# MainBoardR2.net
KiCad netlist of a schematic drawn in EAGLE
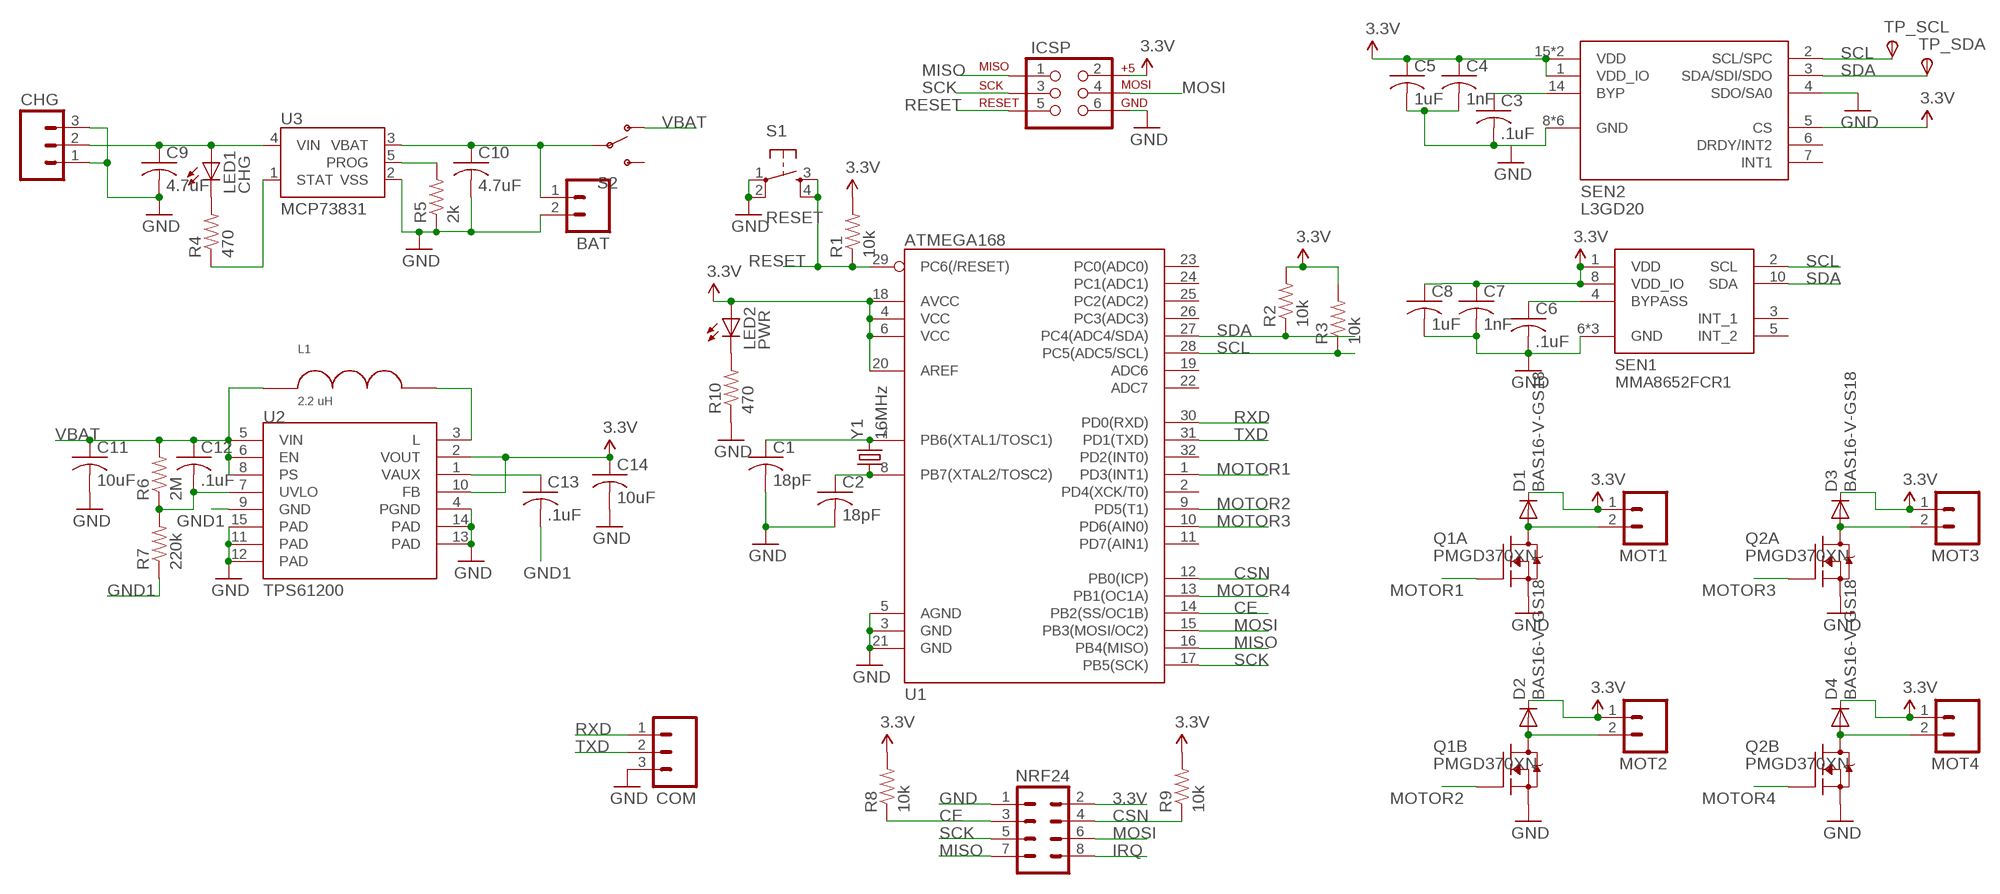
[diagram p0: schematic, sheet 1]

(export (version "E")
  (design (tool "Eeschema 10.0.6"))
  (components
    (comp (ref "BAT")
      (value "M02LOCK_LONGPADS")
      (footprint "eagle-import:1X02_LOCK_LONGPADS")
      (libsource (lib "eagle-import") (part "M02LOCK_LONGPADS"))
    )
    (comp (ref "C1")
      (value "18pF")
      (footprint "eagle-import:C0805")
      (libsource (lib "eagle-import") (part "C-USC0805"))
    )
    (comp (ref "C2")
      (value "18pF")
      (footprint "eagle-import:C0805")
      (libsource (lib "eagle-import") (part "C-USC0805"))
    )
    (comp (ref "C3")
      (value ".1uF")
      (footprint "eagle-import:C0805")
      (libsource (lib "eagle-import") (part "C-USC0805"))
    )
    (comp (ref "C4")
      (value "1nF")
      (footprint "eagle-import:C0805")
      (libsource (lib "eagle-import") (part "C-USC0805"))
    )
    (comp (ref "C5")
      (value "1uF")
      (footprint "eagle-import:C0805")
      (libsource (lib "eagle-import") (part "C-USC0805"))
    )
    (comp (ref "C6")
      (value ".1uF")
      (footprint "eagle-import:C0805")
      (libsource (lib "eagle-import") (part "C-USC0805"))
    )
    (comp (ref "C7")
      (value "1nF")
      (footprint "eagle-import:C0805")
      (libsource (lib "eagle-import") (part "C-USC0805"))
    )
    (comp (ref "C8")
      (value "1uF")
      (footprint "eagle-import:C0805")
      (libsource (lib "eagle-import") (part "C-USC0805"))
    )
    (comp (ref "C9")
      (value "4.7uF")
      (footprint "eagle-import:C0805")
      (libsource (lib "eagle-import") (part "C-USC0805"))
    )
    (comp (ref "C10")
      (value "4.7uF")
      (footprint "eagle-import:C0805")
      (libsource (lib "eagle-import") (part "C-USC0805"))
    )
    (comp (ref "C11")
      (value "10uF")
      (footprint "eagle-import:C0805")
      (libsource (lib "eagle-import") (part "C-USC0805"))
    )
    (comp (ref "C12")
      (value ".1uF")
      (footprint "eagle-import:C0805")
      (libsource (lib "eagle-import") (part "C-USC0805"))
    )
    (comp (ref "C13")
      (value ".1uF")
      (footprint "eagle-import:C0805")
      (libsource (lib "eagle-import") (part "C-USC0805"))
    )
    (comp (ref "C14")
      (value "10uF")
      (footprint "eagle-import:C0805")
      (libsource (lib "eagle-import") (part "C-USC0805"))
    )
    (comp (ref "CHG")
      (value "M03LONGPADS")
      (footprint "eagle-import:1X03_LONGPADS")
      (libsource (lib "eagle-import") (part "M03LONGPADS"))
    )
    (comp (ref "COM")
      (value "M03LONGPADS")
      (footprint "eagle-import:1X03_LONGPADS")
      (libsource (lib "eagle-import") (part "M03LONGPADS"))
    )
    (comp (ref "D1")
      (value "BAS16-V-GS18")
      (footprint "eagle-import:SOT23")
      (libsource (lib "eagle-import") (part "BAS16-V-GS18"))
    )
    (comp (ref "D2")
      (value "BAS16-V-GS18")
      (footprint "eagle-import:SOT23")
      (libsource (lib "eagle-import") (part "BAS16-V-GS18"))
    )
    (comp (ref "D3")
      (value "BAS16-V-GS18")
      (footprint "eagle-import:SOT23")
      (libsource (lib "eagle-import") (part "BAS16-V-GS18"))
    )
    (comp (ref "D4")
      (value "BAS16-V-GS18")
      (footprint "eagle-import:SOT23")
      (libsource (lib "eagle-import") (part "BAS16-V-GS18"))
    )
    (comp (ref "ICSP")
      (value "AVR_SPI_PRG_62X3_LOCK")
      (footprint "eagle-import:2X3_LOCK")
      (libsource (lib "eagle-import") (part "AVR_SPI_PRG_62X3_LOCK"))
    )
    (comp (ref "L1")
      (value "2.2 uH")
      (footprint "eagle-import:2518")
      (libsource (lib "eagle-import") (part "BRHL2518T2R2M"))
    )
    (comp (ref "LED1")
      (value "CHG")
      (footprint "eagle-import:LED-1206")
      (libsource (lib "eagle-import") (part "LED1206"))
    )
    (comp (ref "LED2")
      (value "PWR")
      (footprint "eagle-import:LED-1206")
      (libsource (lib "eagle-import") (part "LED1206"))
    )
    (comp (ref "MOT1")
      (value "M02LOCK_LONGPADS")
      (footprint "eagle-import:1X02_LOCK_LONGPADS")
      (libsource (lib "eagle-import") (part "M02LOCK_LONGPADS"))
    )
    (comp (ref "MOT2")
      (value "M02LOCK_LONGPADS")
      (footprint "eagle-import:1X02_LOCK_LONGPADS")
      (libsource (lib "eagle-import") (part "M02LOCK_LONGPADS"))
    )
    (comp (ref "MOT3")
      (value "M02LOCK_LONGPADS")
      (footprint "eagle-import:1X02_LOCK_LONGPADS")
      (libsource (lib "eagle-import") (part "M02LOCK_LONGPADS"))
    )
    (comp (ref "MOT4")
      (value "M02LOCK_LONGPADS")
      (footprint "eagle-import:1X02_LOCK_LONGPADS")
      (libsource (lib "eagle-import") (part "M02LOCK_LONGPADS"))
    )
    (comp (ref "NRF24")
      (value "M04X2")
      (footprint "eagle-import:2X4")
      (libsource (lib "eagle-import") (part "M04X2"))
    )
    (comp (ref "Q1")
      (value "PMGD370XN")
      (footprint "eagle-import:SOT363_INFINEON")
      (libsource (lib "eagle-import") (part "PMGD370XN"))
    )
    (comp (ref "Q2")
      (value "PMGD370XN")
      (footprint "eagle-import:SOT363_INFINEON")
      (libsource (lib "eagle-import") (part "PMGD370XN"))
    )
    (comp (ref "R1")
      (value "10k")
      (footprint "eagle-import:0805")
      (libsource (lib "eagle-import") (part "RESISTOR0805-RES"))
    )
    (comp (ref "R2")
      (value "10k")
      (footprint "eagle-import:0805")
      (libsource (lib "eagle-import") (part "RESISTOR0805-RES"))
    )
    (comp (ref "R3")
      (value "10k")
      (footprint "eagle-import:0805")
      (libsource (lib "eagle-import") (part "RESISTOR0805-RES"))
    )
    (comp (ref "R4")
      (value "470")
      (footprint "eagle-import:0805")
      (libsource (lib "eagle-import") (part "RESISTOR0805-RES"))
    )
    (comp (ref "R5")
      (value "2k")
      (footprint "eagle-import:0805")
      (libsource (lib "eagle-import") (part "RESISTOR0805-RES"))
    )
    (comp (ref "R6")
      (value "2M")
      (footprint "eagle-import:0805")
      (libsource (lib "eagle-import") (part "RESISTOR0805-RES"))
    )
    (comp (ref "R7")
      (value "220k")
      (footprint "eagle-import:0805")
      (libsource (lib "eagle-import") (part "RESISTOR0805-RES"))
    )
    (comp (ref "R8")
      (value "10k")
      (footprint "eagle-import:0805")
      (libsource (lib "eagle-import") (part "RESISTOR0805-RES"))
    )
    (comp (ref "R9")
      (value "10k")
      (footprint "eagle-import:0805")
      (libsource (lib "eagle-import") (part "RESISTOR0805-RES"))
    )
    (comp (ref "R10")
      (value "470")
      (footprint "eagle-import:0805")
      (libsource (lib "eagle-import") (part "RESISTOR0805-RES"))
    )
    (comp (ref "S1")
      (value "RESET")
      (footprint "eagle-import:TACTILE_SWITCH_SMD")
      (libsource (lib "eagle-import") (part "TAC_SWITCHSMD"))
    )
    (comp (ref "S2")
      (value "SWITCH-SPST-SMD-A")
      (footprint "eagle-import:SWITCH-SPST-SMD-A")
      (libsource (lib "eagle-import") (part "SWITCH-SPST-SMD-A"))
    )
    (comp (ref "SEN1")
      (value "MMA8652FCR1")
      (footprint "eagle-import:10_PIN_DFN")
      (libsource (lib "eagle-import") (part "MMA8652FCR1"))
    )
    (comp (ref "SEN2")
      (value "L3GD20")
      (footprint "eagle-import:LGA-16")
      (libsource (lib "eagle-import") (part "L3GD20"))
    )
    (comp (ref "TP_SCL")
      (value "TPSTP14SQ")
      (footprint "eagle-import:TP14SQ")
      (libsource (lib "eagle-import") (part "TPSTP14SQ"))
    )
    (comp (ref "TP_SDA")
      (value "TPSTP14SQ")
      (footprint "eagle-import:TP14SQ")
      (libsource (lib "eagle-import") (part "TPSTP14SQ"))
    )
    (comp (ref "U1")
      (value "ATMEGA168")
      (footprint "eagle-import:TQFP32-08")
      (libsource (lib "eagle-import") (part "ATMEGA168"))
    )
    (comp (ref "U2")
      (value "TPS61200")
      (footprint "eagle-import:QFN-10_PAD")
      (libsource (lib "eagle-import") (part "TPS61200"))
    )
    (comp (ref "U3")
      (value "MCP73831")
      (footprint "eagle-import:SOT23-5")
      (libsource (lib "eagle-import") (part "MCP73831"))
    )
    (comp (ref "Y1")
      (value "16MHz")
      (footprint "eagle-import:CRYSTAL-SMD-10.5X4.8-2PIN")
      (libsource (lib "eagle-import") (part "CRYSTAL10.5X4.8"))
    )
  )
  (nets
    (net (code "1") (name "/CE") (class "Default")
      (node (ref "NRF24") (pin "3") (pinfunction "3_3") (pintype "passive"))
      (node (ref "R8") (pin "1") (pinfunction "1_1") (pintype "passive"))
      (node (ref "U1") (pin "14") (pinfunction "PB2(SS/OC1B)_14") (pintype "bidirectional"))
    )
    (net (code "2") (name "/CSN") (class "Default")
      (node (ref "NRF24") (pin "4") (pinfunction "4_4") (pintype "passive"))
      (node (ref "R9") (pin "1") (pinfunction "1_1") (pintype "passive"))
      (node (ref "U1") (pin "12") (pinfunction "PB0(ICP)_12") (pintype "bidirectional"))
    )
    (net (code "3") (name "/GND1") (class "Default")
      (node (ref "C13") (pin "2") (pinfunction "2_2") (pintype "passive"))
      (node (ref "R7") (pin "1") (pinfunction "1_1") (pintype "passive"))
      (node (ref "U2") (pin "9") (pinfunction "GND_9") (pintype "power_in"))
    )
    (net (code "4") (name "/IRQ") (class "Default")
      (node (ref "NRF24") (pin "8") (pinfunction "8_8") (pintype "passive"))
    )
    (net (code "5") (name "/MISO") (class "Default")
      (node (ref "ICSP") (pin "1") (pinfunction "1_1") (pintype "passive"))
      (node (ref "NRF24") (pin "7") (pinfunction "7_7") (pintype "passive"))
      (node (ref "U1") (pin "16") (pinfunction "PB4(MISO)_16") (pintype "bidirectional"))
    )
    (net (code "6") (name "/MOSI") (class "Default")
      (node (ref "ICSP") (pin "4") (pinfunction "4_4") (pintype "passive"))
      (node (ref "NRF24") (pin "6") (pinfunction "6_6") (pintype "passive"))
      (node (ref "U1") (pin "15") (pinfunction "PB3(MOSI/OC2)_15") (pintype "bidirectional"))
    )
    (net (code "7") (name "/MOTOR1") (class "Default")
      (node (ref "Q1") (pin "2") (pinfunction "G_2") (pintype "passive"))
      (node (ref "U1") (pin "1") (pinfunction "PD3(INT1)_1") (pintype "bidirectional"))
    )
    (net (code "8") (name "/MOTOR2") (class "Default")
      (node (ref "Q1") (pin "5") (pinfunction "G_5") (pintype "passive"))
      (node (ref "U1") (pin "9") (pinfunction "PD5(T1)_9") (pintype "bidirectional"))
    )
    (net (code "9") (name "/MOTOR3") (class "Default")
      (node (ref "Q2") (pin "2") (pinfunction "G_2") (pintype "passive"))
      (node (ref "U1") (pin "10") (pinfunction "PD6(AIN0)_10") (pintype "bidirectional"))
    )
    (net (code "10") (name "/MOTOR4") (class "Default")
      (node (ref "Q2") (pin "5") (pinfunction "G_5") (pintype "passive"))
      (node (ref "U1") (pin "13") (pinfunction "PB1(OC1A)_13") (pintype "bidirectional"))
    )
    (net (code "11") (name "/RESET") (class "Default")
      (node (ref "ICSP") (pin "5") (pinfunction "5_5") (pintype "passive"))
      (node (ref "R1") (pin "1") (pinfunction "1_1") (pintype "passive"))
      (node (ref "S1") (pin "3") (pinfunction "3_3") (pintype "passive"))
      (node (ref "S1") (pin "4") (pinfunction "4_4") (pintype "passive"))
      (node (ref "U1") (pin "29") (pinfunction "PC6(/RESET)_29") (pintype "bidirectional"))
    )
    (net (code "12") (name "/RXD") (class "Default")
      (node (ref "COM") (pin "1") (pinfunction "1_1") (pintype "passive"))
      (node (ref "U1") (pin "30") (pinfunction "PD0(RXD)_30") (pintype "bidirectional"))
    )
    (net (code "13") (name "/SCK") (class "Default")
      (node (ref "ICSP") (pin "3") (pinfunction "3_3") (pintype "passive"))
      (node (ref "NRF24") (pin "5") (pinfunction "5_5") (pintype "passive"))
      (node (ref "U1") (pin "17") (pinfunction "PB5(SCK)_17") (pintype "bidirectional"))
    )
    (net (code "14") (name "/SCL") (class "Default")
      (node (ref "R3") (pin "1") (pinfunction "1_1") (pintype "passive"))
      (node (ref "SEN1") (pin "2") (pinfunction "SCL_2") (pintype "bidirectional"))
      (node (ref "SEN2") (pin "2") (pinfunction "SCL/SPC_2") (pintype "bidirectional"))
      (node (ref "TP_SCL") (pin "TP") (pinfunction "PP_TP") (pintype "input"))
      (node (ref "U1") (pin "28") (pinfunction "PC5(ADC5/SCL)_28") (pintype "bidirectional"))
    )
    (net (code "15") (name "/SDA") (class "Default")
      (node (ref "R2") (pin "1") (pinfunction "1_1") (pintype "passive"))
      (node (ref "SEN1") (pin "10") (pinfunction "SDA_10") (pintype "bidirectional"))
      (node (ref "SEN2") (pin "3") (pinfunction "SDA/SDI/SDO_3") (pintype "bidirectional"))
      (node (ref "TP_SDA") (pin "TP") (pinfunction "PP_TP") (pintype "input"))
      (node (ref "U1") (pin "27") (pinfunction "PC4(ADC4/SDA)_27") (pintype "bidirectional"))
    )
    (net (code "16") (name "/TXD") (class "Default")
      (node (ref "COM") (pin "2") (pinfunction "2_2") (pintype "passive"))
      (node (ref "U1") (pin "31") (pinfunction "PD1(TXD)_31") (pintype "bidirectional"))
    )
    (net (code "17") (name "/VBAT") (class "Default")
      (node (ref "C11") (pin "1") (pinfunction "1_1") (pintype "passive"))
      (node (ref "C12") (pin "1") (pinfunction "1_1") (pintype "passive"))
      (node (ref "L1") (pin "P$1") (pinfunction "1_P$1") (pintype "bidirectional"))
      (node (ref "R6") (pin "2") (pinfunction "2_2") (pintype "passive"))
      (node (ref "S2") (pin "1") (pinfunction "O_1") (pintype "passive"))
      (node (ref "U2") (pin "5") (pinfunction "VIN_5") (pintype "power_in"))
      (node (ref "U2") (pin "6") (pinfunction "EN_6") (pintype "input"))
      (node (ref "U2") (pin "8") (pinfunction "PS_8") (pintype "input"))
    )
    (net (code "18") (name "3.3V") (class "Default")
      (node (ref "C14") (pin "1") (pinfunction "1_1") (pintype "passive"))
      (node (ref "C4") (pin "1") (pinfunction "1_1") (pintype "passive"))
      (node (ref "C5") (pin "1") (pinfunction "1_1") (pintype "passive"))
      (node (ref "C7") (pin "1") (pinfunction "1_1") (pintype "passive"))
      (node (ref "C8") (pin "1") (pinfunction "1_1") (pintype "passive"))
      (node (ref "D1") (pin "3") (pinfunction "C_3") (pintype "passive"))
      (node (ref "D2") (pin "3") (pinfunction "C_3") (pintype "passive"))
      (node (ref "D3") (pin "3") (pinfunction "C_3") (pintype "passive"))
      (node (ref "D4") (pin "3") (pinfunction "C_3") (pintype "passive"))
      (node (ref "ICSP") (pin "2") (pinfunction "2_2") (pintype "passive"))
      (node (ref "LED2") (pin "A") (pinfunction "A_A") (pintype "passive"))
      (node (ref "MOT1") (pin "1") (pinfunction "1_1") (pintype "passive"))
      (node (ref "MOT2") (pin "1") (pinfunction "1_1") (pintype "passive"))
      (node (ref "MOT3") (pin "1") (pinfunction "1_1") (pintype "passive"))
      (node (ref "MOT4") (pin "1") (pinfunction "1_1") (pintype "passive"))
      (node (ref "NRF24") (pin "2") (pinfunction "2_2") (pintype "passive"))
      (node (ref "R1") (pin "2") (pinfunction "2_2") (pintype "passive"))
      (node (ref "R2") (pin "2") (pinfunction "2_2") (pintype "passive"))
      (node (ref "R3") (pin "2") (pinfunction "2_2") (pintype "passive"))
      (node (ref "R8") (pin "2") (pinfunction "2_2") (pintype "passive"))
      (node (ref "R9") (pin "2") (pinfunction "2_2") (pintype "passive"))
      (node (ref "SEN1") (pin "1") (pinfunction "VDD_1") (pintype "bidirectional"))
      (node (ref "SEN1") (pin "8") (pinfunction "VDD_IO_8") (pintype "bidirectional"))
      (node (ref "SEN2") (pin "1") (pinfunction "VDD_IO_1") (pintype "bidirectional"))
      (node (ref "SEN2") (pin "15") (pinfunction "VDD_15") (pintype "bidirectional"))
      (node (ref "SEN2") (pin "16") (pinfunction "VDD_16") (pintype "bidirectional"))
      (node (ref "SEN2") (pin "5") (pinfunction "CS_5") (pintype "bidirectional"))
      (node (ref "U1") (pin "18") (pinfunction "AVCC_18") (pintype "bidirectional"))
      (node (ref "U1") (pin "20") (pinfunction "AREF_20") (pintype "bidirectional"))
      (node (ref "U1") (pin "4") (pinfunction "VCC_4") (pintype "bidirectional"))
      (node (ref "U1") (pin "6") (pinfunction "VCC_6") (pintype "bidirectional"))
      (node (ref "U2") (pin "10") (pinfunction "FB_10") (pintype "passive"))
      (node (ref "U2") (pin "2") (pinfunction "VOUT_2") (pintype "passive"))
    )
    (net (code "19") (name "GND") (class "Default")
      (node (ref "BAT") (pin "2") (pinfunction "2_2") (pintype "passive"))
      (node (ref "C1") (pin "2") (pinfunction "2_2") (pintype "passive"))
      (node (ref "C10") (pin "2") (pinfunction "2_2") (pintype "passive"))
      (node (ref "C11") (pin "2") (pinfunction "2_2") (pintype "passive"))
      (node (ref "C14") (pin "2") (pinfunction "2_2") (pintype "passive"))
      (node (ref "C2") (pin "2") (pinfunction "2_2") (pintype "passive"))
      (node (ref "C3") (pin "2") (pinfunction "2_2") (pintype "passive"))
      (node (ref "C4") (pin "2") (pinfunction "2_2") (pintype "passive"))
      (node (ref "C5") (pin "2") (pinfunction "2_2") (pintype "passive"))
      (node (ref "C6") (pin "2") (pinfunction "2_2") (pintype "passive"))
      (node (ref "C7") (pin "2") (pinfunction "2_2") (pintype "passive"))
      (node (ref "C8") (pin "2") (pinfunction "2_2") (pintype "passive"))
      (node (ref "C9") (pin "2") (pinfunction "2_2") (pintype "passive"))
      (node (ref "CHG") (pin "1") (pinfunction "1_1") (pintype "passive"))
      (node (ref "CHG") (pin "3") (pinfunction "3_3") (pintype "passive"))
      (node (ref "COM") (pin "3") (pinfunction "3_3") (pintype "passive"))
      (node (ref "ICSP") (pin "6") (pinfunction "6_6") (pintype "passive"))
      (node (ref "NRF24") (pin "1") (pinfunction "1_1") (pintype "passive"))
      (node (ref "Q1") (pin "1") (pinfunction "S_1") (pintype "passive"))
      (node (ref "Q1") (pin "4") (pinfunction "S_4") (pintype "passive"))
      (node (ref "Q2") (pin "1") (pinfunction "S_1") (pintype "passive"))
      (node (ref "Q2") (pin "4") (pinfunction "S_4") (pintype "passive"))
      (node (ref "R10") (pin "1") (pinfunction "1_1") (pintype "passive"))
      (node (ref "R5") (pin "1") (pinfunction "1_1") (pintype "passive"))
      (node (ref "S1") (pin "1") (pinfunction "1_1") (pintype "passive"))
      (node (ref "S1") (pin "2") (pinfunction "2_2") (pintype "passive"))
      (node (ref "SEN1") (pin "6") (pinfunction "GND_6") (pintype "bidirectional"))
      (node (ref "SEN1") (pin "7") (pinfunction "GND_7") (pintype "bidirectional"))
      (node (ref "SEN1") (pin "9") (pinfunction "GND_9") (pintype "bidirectional"))
      (node (ref "SEN2") (pin "10") (pinfunction "GND_10") (pintype "bidirectional"))
      (node (ref "SEN2") (pin "11") (pinfunction "GND_11") (pintype "bidirectional"))
      (node (ref "SEN2") (pin "12") (pinfunction "GND_12") (pintype "bidirectional"))
      (node (ref "SEN2") (pin "13") (pinfunction "GND_13") (pintype "bidirectional"))
      (node (ref "SEN2") (pin "4") (pinfunction "SDO/SA0_4") (pintype "bidirectional"))
      (node (ref "SEN2") (pin "8") (pinfunction "GND_8") (pintype "bidirectional"))
      (node (ref "SEN2") (pin "9") (pinfunction "GND_9") (pintype "bidirectional"))
      (node (ref "U1") (pin "21") (pinfunction "GND_21") (pintype "bidirectional"))
      (node (ref "U1") (pin "3") (pinfunction "GND_3") (pintype "bidirectional"))
      (node (ref "U1") (pin "5") (pinfunction "AGND_5") (pintype "bidirectional"))
      (node (ref "U2") (pin "11") (pinfunction "PAD_11") (pintype "power_in"))
      (node (ref "U2") (pin "12") (pinfunction "PAD_12") (pintype "power_in"))
      (node (ref "U2") (pin "13") (pinfunction "PAD_13") (pintype "power_in"))
      (node (ref "U2") (pin "14") (pinfunction "PAD_14") (pintype "power_in"))
      (node (ref "U2") (pin "15") (pinfunction "PAD_15") (pintype "power_in"))
      (node (ref "U2") (pin "4") (pinfunction "PGND_4") (pintype "power_in"))
      (node (ref "U3") (pin "2") (pinfunction "VSS_2") (pintype "power_in"))
    )
    (net (code "20") (name "Net-(D1-A)") (class "Default")
      (node (ref "D1") (pin "1") (pinfunction "A_1") (pintype "passive"))
      (node (ref "MOT1") (pin "2") (pinfunction "2_2") (pintype "passive"))
      (node (ref "Q1") (pin "6") (pinfunction "D_6") (pintype "passive"))
    )
    (net (code "21") (name "Net-(D2-A)") (class "Default")
      (node (ref "D2") (pin "1") (pinfunction "A_1") (pintype "passive"))
      (node (ref "MOT2") (pin "2") (pinfunction "2_2") (pintype "passive"))
      (node (ref "Q1") (pin "3") (pinfunction "D_3") (pintype "passive"))
    )
    (net (code "22") (name "Net-(D3-A)") (class "Default")
      (node (ref "D3") (pin "1") (pinfunction "A_1") (pintype "passive"))
      (node (ref "MOT3") (pin "2") (pinfunction "2_2") (pintype "passive"))
      (node (ref "Q2") (pin "6") (pinfunction "D_6") (pintype "passive"))
    )
    (net (code "23") (name "Net-(D4-A)") (class "Default")
      (node (ref "D4") (pin "1") (pinfunction "A_1") (pintype "passive"))
      (node (ref "MOT4") (pin "2") (pinfunction "2_2") (pintype "passive"))
      (node (ref "Q2") (pin "3") (pinfunction "D_3") (pintype "passive"))
    )
    (net (code "24") (name "Net-(L1-2)") (class "Default")
      (node (ref "L1") (pin "P$2") (pinfunction "2_P$2") (pintype "bidirectional"))
      (node (ref "U2") (pin "3") (pinfunction "L_3") (pintype "passive"))
    )
    (net (code "25") (name "Net-(LED1-PadC)") (class "Default")
      (node (ref "LED1") (pin "C") (pinfunction "C_C") (pintype "passive"))
      (node (ref "R4") (pin "2") (pinfunction "2_2") (pintype "passive"))
    )
    (net (code "26") (name "Net-(LED2-PadC)") (class "Default")
      (node (ref "LED2") (pin "C") (pinfunction "C_C") (pintype "passive"))
      (node (ref "R10") (pin "2") (pinfunction "2_2") (pintype "passive"))
    )
    (net (code "27") (name "Net-(S2-P)") (class "Default")
      (node (ref "BAT") (pin "1") (pinfunction "1_1") (pintype "passive"))
      (node (ref "C10") (pin "1") (pinfunction "1_1") (pintype "passive"))
      (node (ref "S2") (pin "2") (pinfunction "P_2") (pintype "passive"))
      (node (ref "U3") (pin "3") (pinfunction "VBAT_3") (pintype "power_in"))
    )
    (net (code "28") (name "Net-(SEN1-BYPASS)") (class "Default")
      (node (ref "C6") (pin "1") (pinfunction "1_1") (pintype "passive"))
      (node (ref "SEN1") (pin "4") (pinfunction "BYPASS_4") (pintype "bidirectional"))
    )
    (net (code "29") (name "Net-(SEN2-BYP)") (class "Default")
      (node (ref "C3") (pin "1") (pinfunction "1_1") (pintype "passive"))
      (node (ref "SEN2") (pin "14") (pinfunction "BYP_14") (pintype "bidirectional"))
    )
    (net (code "30") (name "Net-(U1-PB6(XTAL1{slash}TOSC1))") (class "Default")
      (node (ref "C1") (pin "1") (pinfunction "1_1") (pintype "passive"))
      (node (ref "U1") (pin "7") (pinfunction "PB6(XTAL1/TOSC1)_7") (pintype "bidirectional"))
      (node (ref "Y1") (pin "P$2") (pinfunction "2_P$2") (pintype "passive"))
    )
    (net (code "31") (name "Net-(U1-PB7(XTAL2{slash}TOSC2))") (class "Default")
      (node (ref "C2") (pin "1") (pinfunction "1_1") (pintype "passive"))
      (node (ref "U1") (pin "8") (pinfunction "PB7(XTAL2/TOSC2)_8") (pintype "bidirectional"))
      (node (ref "Y1") (pin "P$1") (pinfunction "1_P$1") (pintype "passive"))
    )
    (net (code "32") (name "Net-(U2-UVLO)") (class "Default")
      (node (ref "C12") (pin "2") (pinfunction "2_2") (pintype "passive"))
      (node (ref "R6") (pin "1") (pinfunction "1_1") (pintype "passive"))
      (node (ref "R7") (pin "2") (pinfunction "2_2") (pintype "passive"))
      (node (ref "U2") (pin "7") (pinfunction "UVLO_7") (pintype "passive"))
    )
    (net (code "33") (name "Net-(U2-VAUX)") (class "Default")
      (node (ref "C13") (pin "1") (pinfunction "1_1") (pintype "passive"))
      (node (ref "U2") (pin "1") (pinfunction "VAUX_1") (pintype "passive"))
    )
    (net (code "34") (name "Net-(U3-PROG)") (class "Default")
      (node (ref "R5") (pin "2") (pinfunction "2_2") (pintype "passive"))
      (node (ref "U3") (pin "5") (pinfunction "PROG_5") (pintype "input"))
    )
    (net (code "35") (name "Net-(U3-STAT)") (class "Default")
      (node (ref "R4") (pin "1") (pinfunction "1_1") (pintype "passive"))
      (node (ref "U3") (pin "1") (pinfunction "STAT_1") (pintype "output"))
    )
    (net (code "36") (name "Net-(U3-VIN)") (class "Default")
      (node (ref "C9") (pin "1") (pinfunction "1_1") (pintype "passive"))
      (node (ref "CHG") (pin "2") (pinfunction "2_2") (pintype "passive"))
      (node (ref "LED1") (pin "A") (pinfunction "A_A") (pintype "passive"))
      (node (ref "U3") (pin "4") (pinfunction "VIN_4") (pintype "power_in"))
    )
    (net (code "37") (name "unconnected-(S2-S-Pad3)") (class "Default")
      (node (ref "S2") (pin "3") (pinfunction "S_3") (pintype "passive"))
    )
    (net (code "38") (name "unconnected-(SEN1-INT_1-Pad3)") (class "Default")
      (node (ref "SEN1") (pin "3") (pinfunction "INT_1_3") (pintype "bidirectional"))
    )
    (net (code "39") (name "unconnected-(SEN1-INT_2-Pad5)") (class "Default")
      (node (ref "SEN1") (pin "5") (pinfunction "INT_2_5") (pintype "bidirectional"))
    )
    (net (code "40") (name "unconnected-(SEN2-DRDY{slash}INT2-Pad6)") (class "Default")
      (node (ref "SEN2") (pin "6") (pinfunction "DRDY/INT2_6") (pintype "bidirectional"))
    )
    (net (code "41") (name "unconnected-(SEN2-INT1-Pad7)") (class "Default")
      (node (ref "SEN2") (pin "7") (pinfunction "INT1_7") (pintype "bidirectional"))
    )
    (net (code "42") (name "unconnected-(U1-ADC6-Pad19)") (class "Default")
      (node (ref "U1") (pin "19") (pinfunction "ADC6_19") (pintype "bidirectional"))
    )
    (net (code "43") (name "unconnected-(U1-ADC7-Pad22)") (class "Default")
      (node (ref "U1") (pin "22") (pinfunction "ADC7_22") (pintype "bidirectional"))
    )
    (net (code "44") (name "unconnected-(U1-PC0(ADC0)-Pad23)") (class "Default")
      (node (ref "U1") (pin "23") (pinfunction "PC0(ADC0)_23") (pintype "bidirectional"))
    )
    (net (code "45") (name "unconnected-(U1-PC1(ADC1)-Pad24)") (class "Default")
      (node (ref "U1") (pin "24") (pinfunction "PC1(ADC1)_24") (pintype "bidirectional"))
    )
    (net (code "46") (name "unconnected-(U1-PC2(ADC2)-Pad25)") (class "Default")
      (node (ref "U1") (pin "25") (pinfunction "PC2(ADC2)_25") (pintype "bidirectional"))
    )
    (net (code "47") (name "unconnected-(U1-PC3(ADC3)-Pad26)") (class "Default")
      (node (ref "U1") (pin "26") (pinfunction "PC3(ADC3)_26") (pintype "bidirectional"))
    )
    (net (code "48") (name "unconnected-(U1-PD2(INT0)-Pad32)") (class "Default")
      (node (ref "U1") (pin "32") (pinfunction "PD2(INT0)_32") (pintype "bidirectional"))
    )
    (net (code "49") (name "unconnected-(U1-PD4(XCK{slash}T0)-Pad2)") (class "Default")
      (node (ref "U1") (pin "2") (pinfunction "PD4(XCK/T0)_2") (pintype "bidirectional"))
    )
    (net (code "50") (name "unconnected-(U1-PD7(AIN1)-Pad11)") (class "Default")
      (node (ref "U1") (pin "11") (pinfunction "PD7(AIN1)_11") (pintype "bidirectional"))
    )
  )
)
